# ce3_redraw.net
KiCad netlist of a schematic drawn in EAGLE
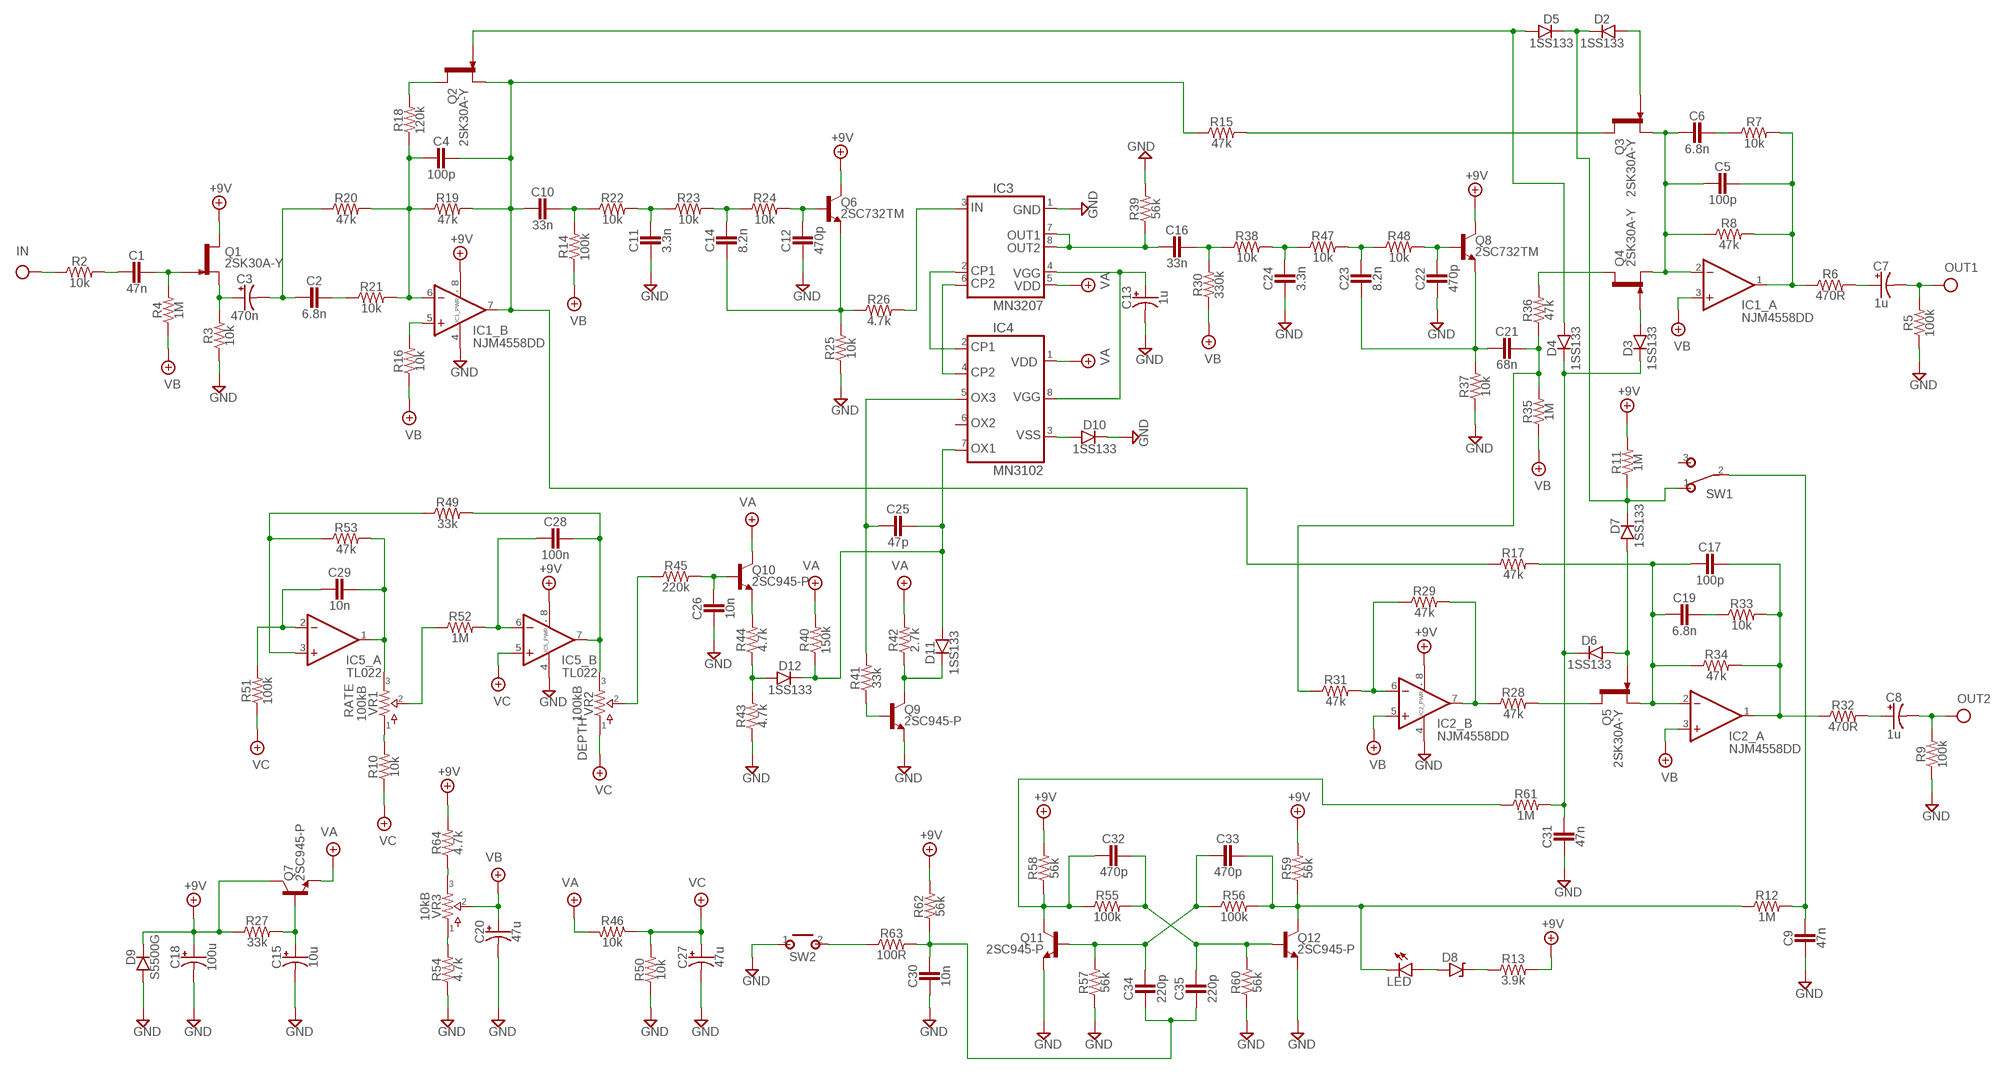
[diagram p0: schematic, sheet 1]

(export (version "E")
  (design (tool "Eeschema 10.0.6"))
  (components
    (comp (ref "C1")
      (value "47n")
      (footprint "eagle-import:BOX_SMALL")
      (libsource (lib "eagle-import") (part "CER/FILMBOX.1"))
    )
    (comp (ref "C2")
      (value "6.8n")
      (footprint "eagle-import:BOX_SMALL")
      (libsource (lib "eagle-import") (part "CER/FILMBOX.1"))
    )
    (comp (ref "C3")
      (value "470n")
      (footprint "eagle-import:040_020")
      (libsource (lib "eagle-import") (part "0400"))
    )
    (comp (ref "C4")
      (value "100p")
      (footprint "eagle-import:BOX_SMALL")
      (libsource (lib "eagle-import") (part "CER/FILMBOX.1"))
    )
    (comp (ref "C5")
      (value "100p")
      (footprint "eagle-import:BOX_SMALL")
      (libsource (lib "eagle-import") (part "CER/FILMBOX.1"))
    )
    (comp (ref "C6")
      (value "6.8n")
      (footprint "eagle-import:BOX_SMALL")
      (libsource (lib "eagle-import") (part "CER/FILMBOX.1"))
    )
    (comp (ref "C7")
      (value "1u")
      (footprint "eagle-import:040_020")
      (libsource (lib "eagle-import") (part "0400"))
    )
    (comp (ref "C8")
      (value "1u")
      (footprint "eagle-import:040_020")
      (libsource (lib "eagle-import") (part "0400"))
    )
    (comp (ref "C9")
      (value "47n")
      (footprint "eagle-import:BOX_SMALL")
      (libsource (lib "eagle-import") (part "CER/FILMBOX.1"))
    )
    (comp (ref "C10")
      (value "33n")
      (footprint "eagle-import:BOX_SMALL")
      (libsource (lib "eagle-import") (part "CER/FILMBOX.1"))
    )
    (comp (ref "C11")
      (value "3.3n")
      (footprint "eagle-import:BOX_SMALL")
      (libsource (lib "eagle-import") (part "CER/FILMBOX.1"))
    )
    (comp (ref "C12")
      (value "470p")
      (footprint "eagle-import:BOX_SMALL")
      (libsource (lib "eagle-import") (part "CER/FILMBOX.1"))
    )
    (comp (ref "C13")
      (value "1u")
      (footprint "eagle-import:040_020")
      (libsource (lib "eagle-import") (part "0400"))
    )
    (comp (ref "C14")
      (value "8.2n")
      (footprint "eagle-import:BOX_SMALL")
      (libsource (lib "eagle-import") (part "CER/FILMBOX.1"))
    )
    (comp (ref "C15")
      (value "10u")
      (footprint "eagle-import:040_020")
      (libsource (lib "eagle-import") (part "0400"))
    )
    (comp (ref "C16")
      (value "33n")
      (footprint "eagle-import:BOX_SMALL")
      (libsource (lib "eagle-import") (part "CER/FILMBOX.1"))
    )
    (comp (ref "C17")
      (value "100p")
      (footprint "eagle-import:BOX_SMALL")
      (libsource (lib "eagle-import") (part "CER/FILMBOX.1"))
    )
    (comp (ref "C18")
      (value "100u")
      (footprint "eagle-import:040_020")
      (libsource (lib "eagle-import") (part "0400"))
    )
    (comp (ref "C19")
      (value "6.8n")
      (footprint "eagle-import:BOX_SMALL")
      (libsource (lib "eagle-import") (part "CER/FILMBOX.1"))
    )
    (comp (ref "C20")
      (value "47u")
      (footprint "eagle-import:040_020")
      (libsource (lib "eagle-import") (part "0400"))
    )
    (comp (ref "C21")
      (value "68n")
      (footprint "eagle-import:BOX_SMALL")
      (libsource (lib "eagle-import") (part "CER/FILMBOX.1"))
    )
    (comp (ref "C22")
      (value "470p")
      (footprint "eagle-import:BOX_SMALL")
      (libsource (lib "eagle-import") (part "CER/FILMBOX.1"))
    )
    (comp (ref "C23")
      (value "8.2n")
      (footprint "eagle-import:BOX_SMALL")
      (libsource (lib "eagle-import") (part "CER/FILMBOX.1"))
    )
    (comp (ref "C24")
      (value "3.3n")
      (footprint "eagle-import:BOX_SMALL")
      (libsource (lib "eagle-import") (part "CER/FILMBOX.1"))
    )
    (comp (ref "C25")
      (value "47p")
      (footprint "eagle-import:BOX_SMALL")
      (libsource (lib "eagle-import") (part "CER/FILMBOX.1"))
    )
    (comp (ref "C26")
      (value "10n")
      (footprint "eagle-import:BOX_SMALL")
      (libsource (lib "eagle-import") (part "CER/FILMBOX.1"))
    )
    (comp (ref "C27")
      (value "47u")
      (footprint "eagle-import:040_020")
      (libsource (lib "eagle-import") (part "0400"))
    )
    (comp (ref "C28")
      (value "100n")
      (footprint "eagle-import:BOX_SMALL")
      (libsource (lib "eagle-import") (part "CER/FILMBOX.1"))
    )
    (comp (ref "C29")
      (value "10n")
      (footprint "eagle-import:BOX_SMALL")
      (libsource (lib "eagle-import") (part "CER/FILMBOX.1"))
    )
    (comp (ref "C30")
      (value "10n")
      (footprint "eagle-import:BOX_SMALL")
      (libsource (lib "eagle-import") (part "CER/FILMBOX.1"))
    )
    (comp (ref "C31")
      (value "47n")
      (footprint "eagle-import:BOX_SMALL")
      (libsource (lib "eagle-import") (part "CER/FILMBOX.1"))
    )
    (comp (ref "C32")
      (value "470p")
      (footprint "eagle-import:BOX_SMALL")
      (libsource (lib "eagle-import") (part "CER/FILMBOX.1"))
    )
    (comp (ref "C33")
      (value "470p")
      (footprint "eagle-import:BOX_SMALL")
      (libsource (lib "eagle-import") (part "CER/FILMBOX.1"))
    )
    (comp (ref "C34")
      (value "220p")
      (footprint "eagle-import:BOX_SMALL")
      (libsource (lib "eagle-import") (part "CER/FILMBOX.1"))
    )
    (comp (ref "C35")
      (value "220p")
      (footprint "eagle-import:BOX_SMALL")
      (libsource (lib "eagle-import") (part "CER/FILMBOX.1"))
    )
    (comp (ref "D2")
      (value "1SS133")
      (footprint "eagle-import:DO35-2")
      (libsource (lib "eagle-import") (part "DO35.2"))
    )
    (comp (ref "D3")
      (value "1SS133")
      (footprint "eagle-import:DO35-2")
      (libsource (lib "eagle-import") (part "DO35.2"))
    )
    (comp (ref "D4")
      (value "1SS133")
      (footprint "eagle-import:DO35-2")
      (libsource (lib "eagle-import") (part "DO35.2"))
    )
    (comp (ref "D5")
      (value "1SS133")
      (footprint "eagle-import:DO35-2")
      (libsource (lib "eagle-import") (part "DO35.2"))
    )
    (comp (ref "D6")
      (value "1SS133")
      (footprint "eagle-import:DO35-2")
      (libsource (lib "eagle-import") (part "DO35.2"))
    )
    (comp (ref "D7")
      (value "1SS133")
      (footprint "eagle-import:DO35-2")
      (libsource (lib "eagle-import") (part "DO35.2"))
    )
    (comp (ref "D8")
      (value "ZENER.2")
      (footprint "eagle-import:DO41-2")
      (libsource (lib "eagle-import") (part "ZENER.2"))
    )
    (comp (ref "D9")
      (value "S5500G")
      (footprint "eagle-import:DO35-2")
      (libsource (lib "eagle-import") (part "DO35.2"))
    )
    (comp (ref "D10")
      (value "1SS133")
      (footprint "eagle-import:DO35-2")
      (libsource (lib "eagle-import") (part "DO35.2"))
    )
    (comp (ref "D11")
      (value "1SS133")
      (footprint "eagle-import:DO35-2")
      (libsource (lib "eagle-import") (part "DO35.2"))
    )
    (comp (ref "D12")
      (value "1SS133")
      (footprint "eagle-import:DO35-2")
      (libsource (lib "eagle-import") (part "DO35.2"))
    )
    (comp (ref "IC1")
      (value "NJM4558DD")
      (footprint "eagle-import:DIL0")
      (libsource (lib "eagle-import") (part "DUALTH"))
    )
    (comp (ref "IC2")
      (value "NJM4558DD")
      (footprint "eagle-import:DIL0")
      (libsource (lib "eagle-import") (part "DUALTH"))
    )
    (comp (ref "IC3")
      (value "MN3207")
      (footprint "eagle-import:DIL0")
      (libsource (lib "eagle-import") (part "BL3208"))
    )
    (comp (ref "IC4")
      (value "MN3102")
      (footprint "eagle-import:DIL8")
      (libsource (lib "eagle-import") (part "CLOCK"))
    )
    (comp (ref "IC5")
      (value "TL022")
      (footprint "eagle-import:DIL0")
      (libsource (lib "eagle-import") (part "DUALTH"))
    )
    (comp (ref "LED")
      (value "LED")
      (footprint "eagle-import:3MM_D")
      (libsource (lib "eagle-import") (part "LED"))
    )
    (comp (ref "Q1")
      (value "2SK30A-Y")
      (footprint "eagle-import:TO92-")
      (libsource (lib "eagle-import") (part "2N5457"))
    )
    (comp (ref "Q2")
      (value "2SK30A-Y")
      (footprint "eagle-import:TO92-")
      (libsource (lib "eagle-import") (part "2N5457"))
    )
    (comp (ref "Q3")
      (value "2SK30A-Y")
      (footprint "eagle-import:TO92-")
      (libsource (lib "eagle-import") (part "2N5457"))
    )
    (comp (ref "Q4")
      (value "2SK30A-Y")
      (footprint "eagle-import:TO92-")
      (libsource (lib "eagle-import") (part "2N5457"))
    )
    (comp (ref "Q5")
      (value "2SK30A-Y")
      (footprint "eagle-import:TO92-")
      (libsource (lib "eagle-import") (part "2N5457"))
    )
    (comp (ref "Q6")
      (value "2SC732TM")
      (footprint "eagle-import:TO92-")
      (libsource (lib "eagle-import") (part "2SC828A"))
    )
    (comp (ref "Q7")
      (value "2SC945-P")
      (footprint "eagle-import:TO92-")
      (libsource (lib "eagle-import") (part "2SC828A"))
    )
    (comp (ref "Q8")
      (value "2SC732TM")
      (footprint "eagle-import:TO92-")
      (libsource (lib "eagle-import") (part "2SC828A"))
    )
    (comp (ref "Q9")
      (value "2SC945-P")
      (footprint "eagle-import:TO92-")
      (libsource (lib "eagle-import") (part "2SC828A"))
    )
    (comp (ref "Q10")
      (value "2SC945-P")
      (footprint "eagle-import:TO92-")
      (libsource (lib "eagle-import") (part "2SC828A"))
    )
    (comp (ref "Q11")
      (value "2SC945-P")
      (footprint "eagle-import:TO92-")
      (libsource (lib "eagle-import") (part "2SC828A"))
    )
    (comp (ref "Q12")
      (value "2SC945-P")
      (footprint "eagle-import:TO92-")
      (libsource (lib "eagle-import") (part "2SC828A"))
    )
    (comp (ref "R2")
      (value "10k")
      (footprint "eagle-import:R0207_3")
      (libsource (lib "eagle-import") (part "R_.3B"))
    )
    (comp (ref "R3")
      (value "10k")
      (footprint "eagle-import:R0207_3")
      (libsource (lib "eagle-import") (part "R_.3B"))
    )
    (comp (ref "R4")
      (value "1M")
      (footprint "eagle-import:R0207_3")
      (libsource (lib "eagle-import") (part "R_.3B"))
    )
    (comp (ref "R5")
      (value "100k")
      (footprint "eagle-import:R0207_3")
      (libsource (lib "eagle-import") (part "R_.3B"))
    )
    (comp (ref "R6")
      (value "470R")
      (footprint "eagle-import:R0207_3")
      (libsource (lib "eagle-import") (part "R_.3B"))
    )
    (comp (ref "R7")
      (value "10k")
      (footprint "eagle-import:R0207_3")
      (libsource (lib "eagle-import") (part "R_.3B"))
    )
    (comp (ref "R8")
      (value "47k")
      (footprint "eagle-import:R0207_3")
      (libsource (lib "eagle-import") (part "R_.3B"))
    )
    (comp (ref "R9")
      (value "100k")
      (footprint "eagle-import:R0207_3")
      (libsource (lib "eagle-import") (part "R_.3B"))
    )
    (comp (ref "R10")
      (value "10k")
      (footprint "eagle-import:R0207_3")
      (libsource (lib "eagle-import") (part "R_.3B"))
    )
    (comp (ref "R11")
      (value "1M")
      (footprint "eagle-import:R0207_3")
      (libsource (lib "eagle-import") (part "R_.3B"))
    )
    (comp (ref "R12")
      (value "1M")
      (footprint "eagle-import:R0207_3")
      (libsource (lib "eagle-import") (part "R_.3B"))
    )
    (comp (ref "R13")
      (value "3.9k")
      (footprint "eagle-import:R0207_3")
      (libsource (lib "eagle-import") (part "R_.3B"))
    )
    (comp (ref "R14")
      (value "100k")
      (footprint "eagle-import:R0207_3")
      (libsource (lib "eagle-import") (part "R_.3B"))
    )
    (comp (ref "R15")
      (value "47k")
      (footprint "eagle-import:R0207_3")
      (libsource (lib "eagle-import") (part "R_.3B"))
    )
    (comp (ref "R16")
      (value "10k")
      (footprint "eagle-import:R0207_3")
      (libsource (lib "eagle-import") (part "R_.3B"))
    )
    (comp (ref "R17")
      (value "47k")
      (footprint "eagle-import:R0207_3")
      (libsource (lib "eagle-import") (part "R_.3B"))
    )
    (comp (ref "R18")
      (value "120k")
      (footprint "eagle-import:R0207_3")
      (libsource (lib "eagle-import") (part "R_.3B"))
    )
    (comp (ref "R19")
      (value "47k")
      (footprint "eagle-import:R0207_3")
      (libsource (lib "eagle-import") (part "R_.3B"))
    )
    (comp (ref "R20")
      (value "47k")
      (footprint "eagle-import:R0207_3")
      (libsource (lib "eagle-import") (part "R_.3B"))
    )
    (comp (ref "R21")
      (value "10k")
      (footprint "eagle-import:R0207_3")
      (libsource (lib "eagle-import") (part "R_.3B"))
    )
    (comp (ref "R22")
      (value "10k")
      (footprint "eagle-import:R0207_3")
      (libsource (lib "eagle-import") (part "R_.3B"))
    )
    (comp (ref "R23")
      (value "10k")
      (footprint "eagle-import:R0207_3")
      (libsource (lib "eagle-import") (part "R_.3B"))
    )
    (comp (ref "R24")
      (value "10k")
      (footprint "eagle-import:R0207_3")
      (libsource (lib "eagle-import") (part "R_.3B"))
    )
    (comp (ref "R25")
      (value "10k")
      (footprint "eagle-import:R0207_3")
      (libsource (lib "eagle-import") (part "R_.3B"))
    )
    (comp (ref "R26")
      (value "4.7k")
      (footprint "eagle-import:R0207_3")
      (libsource (lib "eagle-import") (part "R_.3B"))
    )
    (comp (ref "R27")
      (value "33k")
      (footprint "eagle-import:R0207_3")
      (libsource (lib "eagle-import") (part "R_.3B"))
    )
    (comp (ref "R28")
      (value "47k")
      (footprint "eagle-import:R0207_3")
      (libsource (lib "eagle-import") (part "R_.3B"))
    )
    (comp (ref "R29")
      (value "47k")
      (footprint "eagle-import:R0207_3")
      (libsource (lib "eagle-import") (part "R_.3B"))
    )
    (comp (ref "R30")
      (value "330k")
      (footprint "eagle-import:R0207_3")
      (libsource (lib "eagle-import") (part "R_.3B"))
    )
    (comp (ref "R31")
      (value "47k")
      (footprint "eagle-import:R0207_3")
      (libsource (lib "eagle-import") (part "R_.3B"))
    )
    (comp (ref "R32")
      (value "470R")
      (footprint "eagle-import:R0207_3")
      (libsource (lib "eagle-import") (part "R_.3B"))
    )
    (comp (ref "R33")
      (value "10k")
      (footprint "eagle-import:R0207_3")
      (libsource (lib "eagle-import") (part "R_.3B"))
    )
    (comp (ref "R34")
      (value "47k")
      (footprint "eagle-import:R0207_3")
      (libsource (lib "eagle-import") (part "R_.3B"))
    )
    (comp (ref "R35")
      (value "1M")
      (footprint "eagle-import:R0207_3")
      (libsource (lib "eagle-import") (part "R_.3B"))
    )
    (comp (ref "R36")
      (value "47k")
      (footprint "eagle-import:R0207_3")
      (libsource (lib "eagle-import") (part "R_.3B"))
    )
    (comp (ref "R37")
      (value "10k")
      (footprint "eagle-import:R0207_3")
      (libsource (lib "eagle-import") (part "R_.3B"))
    )
    (comp (ref "R38")
      (value "10k")
      (footprint "eagle-import:R0207_3")
      (libsource (lib "eagle-import") (part "R_.3B"))
    )
    (comp (ref "R39")
      (value "56k")
      (footprint "eagle-import:R0207_3")
      (libsource (lib "eagle-import") (part "R_.3B"))
    )
    (comp (ref "R40")
      (value "150k")
      (footprint "eagle-import:R0207_3")
      (libsource (lib "eagle-import") (part "R_.3B"))
    )
    (comp (ref "R41")
      (value "33k")
      (footprint "eagle-import:R0207_3")
      (libsource (lib "eagle-import") (part "R_.3B"))
    )
    (comp (ref "R42")
      (value "2.7k")
      (footprint "eagle-import:R0207_3")
      (libsource (lib "eagle-import") (part "R_.3B"))
    )
    (comp (ref "R43")
      (value "4.7k")
      (footprint "eagle-import:R0207_3")
      (libsource (lib "eagle-import") (part "R_.3B"))
    )
    (comp (ref "R44")
      (value "4.7k")
      (footprint "eagle-import:R0207_3")
      (libsource (lib "eagle-import") (part "R_.3B"))
    )
    (comp (ref "R45")
      (value "220k")
      (footprint "eagle-import:R0207_3")
      (libsource (lib "eagle-import") (part "R_.3B"))
    )
    (comp (ref "R46")
      (value "10k")
      (footprint "eagle-import:R0207_3")
      (libsource (lib "eagle-import") (part "R_.3B"))
    )
    (comp (ref "R47")
      (value "10k")
      (footprint "eagle-import:R0207_3")
      (libsource (lib "eagle-import") (part "R_.3B"))
    )
    (comp (ref "R48")
      (value "10k")
      (footprint "eagle-import:R0207_3")
      (libsource (lib "eagle-import") (part "R_.3B"))
    )
    (comp (ref "R49")
      (value "33k")
      (footprint "eagle-import:R0207_3")
      (libsource (lib "eagle-import") (part "R_.3B"))
    )
    (comp (ref "R50")
      (value "10k")
      (footprint "eagle-import:R0207_3")
      (libsource (lib "eagle-import") (part "R_.3B"))
    )
    (comp (ref "R51")
      (value "100k")
      (footprint "eagle-import:R0207_3")
      (libsource (lib "eagle-import") (part "R_.3B"))
    )
    (comp (ref "R52")
      (value "1M")
      (footprint "eagle-import:R0207_3")
      (libsource (lib "eagle-import") (part "R_.3B"))
    )
    (comp (ref "R53")
      (value "47k")
      (footprint "eagle-import:R0207_3")
      (libsource (lib "eagle-import") (part "R_.3B"))
    )
    (comp (ref "R54")
      (value "4.7k")
      (footprint "eagle-import:R0207_3")
      (libsource (lib "eagle-import") (part "R_.3B"))
    )
    (comp (ref "R55")
      (value "100k")
      (footprint "eagle-import:R0207_3")
      (libsource (lib "eagle-import") (part "R_.3B"))
    )
    (comp (ref "R56")
      (value "100k")
      (footprint "eagle-import:R0207_3")
      (libsource (lib "eagle-import") (part "R_.3B"))
    )
    (comp (ref "R57")
      (value "56k")
      (footprint "eagle-import:R0207_3")
      (libsource (lib "eagle-import") (part "R_.3B"))
    )
    (comp (ref "R58")
      (value "56k")
      (footprint "eagle-import:R0207_3")
      (libsource (lib "eagle-import") (part "R_.3B"))
    )
    (comp (ref "R59")
      (value "56k")
      (footprint "eagle-import:R0207_3")
      (libsource (lib "eagle-import") (part "R_.3B"))
    )
    (comp (ref "R60")
      (value "56k")
      (footprint "eagle-import:R0207_3")
      (libsource (lib "eagle-import") (part "R_.3B"))
    )
    (comp (ref "R61")
      (value "1M")
      (footprint "eagle-import:R0207_3")
      (libsource (lib "eagle-import") (part "R_.3B"))
    )
    (comp (ref "R62")
      (value "56k")
      (footprint "eagle-import:R0207_3")
      (libsource (lib "eagle-import") (part "R_.3B"))
    )
    (comp (ref "R63")
      (value "100R")
      (footprint "eagle-import:R0207_3")
      (libsource (lib "eagle-import") (part "R_.3B"))
    )
    (comp (ref "R64")
      (value "4.7k")
      (footprint "eagle-import:R0207_3")
      (libsource (lib "eagle-import") (part "R_.3B"))
    )
    (comp (ref "SW1")
      (value "SPDT")
      (footprint "eagle-import:M9040P")
      (libsource (lib "eagle-import") (part "SPDT"))
    )
    (comp (ref "SW2")
      (value "MOMENTARY")
      (footprint "eagle-import:SPST")
      (libsource (lib "eagle-import") (part "MOMENTARY"))
    )
    (comp (ref "VR1")
      (value "100kB")
      (footprint "eagle-import:16MM")
      (libsource (lib "eagle-import") (part "POTS16MM"))
    )
    (comp (ref "VR2")
      (value "100kB")
      (footprint "eagle-import:16MM")
      (libsource (lib "eagle-import") (part "POTS16MM"))
    )
    (comp (ref "VR3")
      (value "10kB")
      (footprint "eagle-import:16MM")
      (libsource (lib "eagle-import") (part "POTS16MM"))
    )
  )
  (nets
    (net (code "1") (name "+9V") (class "Default")
      (node (ref "C18") (pin "+") (pinfunction "+_+") (pintype "passive"))
      (node (ref "D9") (pin "C") (pinfunction "C_C") (pintype "passive"))
      (node (ref "IC1") (pin "8") (pinfunction "V+_8") (pintype "power_in"))
      (node (ref "IC2") (pin "8") (pinfunction "V+_8") (pintype "power_in"))
      (node (ref "IC5") (pin "8") (pinfunction "V+_8") (pintype "power_in"))
      (node (ref "Q1") (pin "3") (pinfunction "D_3") (pintype "passive"))
      (node (ref "Q6") (pin "2") (pinfunction "C_2") (pintype "passive"))
      (node (ref "Q7") (pin "2") (pinfunction "C_2") (pintype "passive"))
      (node (ref "Q8") (pin "2") (pinfunction "C_2") (pintype "passive"))
      (node (ref "R11") (pin "2") (pinfunction "2_2") (pintype "passive"))
      (node (ref "R13") (pin "2") (pinfunction "2_2") (pintype "passive"))
      (node (ref "R27") (pin "1") (pinfunction "1_1") (pintype "passive"))
      (node (ref "R58") (pin "2") (pinfunction "2_2") (pintype "passive"))
      (node (ref "R59") (pin "2") (pinfunction "2_2") (pintype "passive"))
      (node (ref "R62") (pin "2") (pinfunction "2_2") (pintype "passive"))
      (node (ref "R64") (pin "2") (pinfunction "2_2") (pintype "passive"))
    )
    (net (code "2") (name "GND") (class "Default")
      (node (ref "C11") (pin "2") (pinfunction "2_2") (pintype "passive"))
      (node (ref "C12") (pin "2") (pinfunction "2_2") (pintype "passive"))
      (node (ref "C13") (pin "-") (pinfunction "-_-") (pintype "passive"))
      (node (ref "C15") (pin "-") (pinfunction "-_-") (pintype "passive"))
      (node (ref "C18") (pin "-") (pinfunction "-_-") (pintype "passive"))
      (node (ref "C20") (pin "-") (pinfunction "-_-") (pintype "passive"))
      (node (ref "C22") (pin "2") (pinfunction "2_2") (pintype "passive"))
      (node (ref "C24") (pin "2") (pinfunction "2_2") (pintype "passive"))
      (node (ref "C26") (pin "2") (pinfunction "2_2") (pintype "passive"))
      (node (ref "C27") (pin "-") (pinfunction "-_-") (pintype "passive"))
      (node (ref "C30") (pin "2") (pinfunction "2_2") (pintype "passive"))
      (node (ref "C31") (pin "2") (pinfunction "2_2") (pintype "passive"))
      (node (ref "C9") (pin "2") (pinfunction "2_2") (pintype "passive"))
      (node (ref "D10") (pin "C") (pinfunction "C_C") (pintype "passive"))
      (node (ref "D9") (pin "A") (pinfunction "A_A") (pintype "passive"))
      (node (ref "IC1") (pin "4") (pinfunction "V-_4") (pintype "power_in"))
      (node (ref "IC2") (pin "4") (pinfunction "V-_4") (pintype "power_in"))
      (node (ref "IC3") (pin "1") (pinfunction "1_1") (pintype "bidirectional"))
      (node (ref "IC5") (pin "4") (pinfunction "V-_4") (pintype "power_in"))
      (node (ref "Q11") (pin "3") (pinfunction "E_3") (pintype "passive"))
      (node (ref "Q12") (pin "3") (pinfunction "E_3") (pintype "passive"))
      (node (ref "Q9") (pin "3") (pinfunction "E_3") (pintype "passive"))
      (node (ref "R25") (pin "1") (pinfunction "1_1") (pintype "passive"))
      (node (ref "R3") (pin "1") (pinfunction "1_1") (pintype "passive"))
      (node (ref "R37") (pin "1") (pinfunction "1_1") (pintype "passive"))
      (node (ref "R39") (pin "2") (pinfunction "2_2") (pintype "passive"))
      (node (ref "R43") (pin "1") (pinfunction "1_1") (pintype "passive"))
      (node (ref "R5") (pin "1") (pinfunction "1_1") (pintype "passive"))
      (node (ref "R50") (pin "1") (pinfunction "1_1") (pintype "passive"))
      (node (ref "R54") (pin "1") (pinfunction "1_1") (pintype "passive"))
      (node (ref "R57") (pin "1") (pinfunction "1_1") (pintype "passive"))
      (node (ref "R60") (pin "1") (pinfunction "1_1") (pintype "passive"))
      (node (ref "R9") (pin "1") (pinfunction "1_1") (pintype "passive"))
      (node (ref "SW2") (pin "1") (pinfunction "P_1") (pintype "passive"))
    )
    (net (code "3") (name "IN") (class "Default")
      (node (ref "R2") (pin "1") (pinfunction "1_1") (pintype "passive"))
    )
    (net (code "4") (name "Net-(C1-Pad2)") (class "Default")
      (node (ref "C1") (pin "2") (pinfunction "2_2") (pintype "passive"))
      (node (ref "R2") (pin "2") (pinfunction "2_2") (pintype "passive"))
    )
    (net (code "5") (name "Net-(C2-Pad1)") (class "Default")
      (node (ref "C2") (pin "1") (pinfunction "1_1") (pintype "passive"))
      (node (ref "R21") (pin "1") (pinfunction "1_1") (pintype "passive"))
    )
    (net (code "6") (name "Net-(C2-Pad2)") (class "Default")
      (node (ref "C2") (pin "2") (pinfunction "2_2") (pintype "passive"))
      (node (ref "C3") (pin "-") (pinfunction "-_-") (pintype "passive"))
      (node (ref "R20") (pin "1") (pinfunction "1_1") (pintype "passive"))
    )
    (net (code "7") (name "Net-(C6-Pad1)") (class "Default")
      (node (ref "C6") (pin "1") (pinfunction "1_1") (pintype "passive"))
      (node (ref "R7") (pin "1") (pinfunction "1_1") (pintype "passive"))
    )
    (net (code "8") (name "Net-(C7-Pad+)") (class "Default")
      (node (ref "C7") (pin "+") (pinfunction "+_+") (pintype "passive"))
      (node (ref "R6") (pin "2") (pinfunction "2_2") (pintype "passive"))
    )
    (net (code "9") (name "Net-(C8-Pad+)") (class "Default")
      (node (ref "C8") (pin "+") (pinfunction "+_+") (pintype "passive"))
      (node (ref "R32") (pin "2") (pinfunction "2_2") (pintype "passive"))
    )
    (net (code "10") (name "Net-(C10-Pad1)") (class "Default")
      (node (ref "C10") (pin "1") (pinfunction "1_1") (pintype "passive"))
      (node (ref "R14") (pin "2") (pinfunction "2_2") (pintype "passive"))
      (node (ref "R22") (pin "1") (pinfunction "1_1") (pintype "passive"))
    )
    (net (code "11") (name "Net-(C11-Pad1)") (class "Default")
      (node (ref "C11") (pin "1") (pinfunction "1_1") (pintype "passive"))
      (node (ref "R22") (pin "2") (pinfunction "2_2") (pintype "passive"))
      (node (ref "R23") (pin "1") (pinfunction "1_1") (pintype "passive"))
    )
    (net (code "12") (name "Net-(C14-Pad1)") (class "Default")
      (node (ref "C14") (pin "1") (pinfunction "1_1") (pintype "passive"))
      (node (ref "R23") (pin "2") (pinfunction "2_2") (pintype "passive"))
      (node (ref "R24") (pin "1") (pinfunction "1_1") (pintype "passive"))
    )
    (net (code "13") (name "Net-(C16-Pad1)") (class "Default")
      (node (ref "C16") (pin "1") (pinfunction "1_1") (pintype "passive"))
      (node (ref "R30") (pin "2") (pinfunction "2_2") (pintype "passive"))
      (node (ref "R38") (pin "1") (pinfunction "1_1") (pintype "passive"))
    )
    (net (code "14") (name "Net-(C16-Pad2)") (class "Default")
      (node (ref "C16") (pin "2") (pinfunction "2_2") (pintype "passive"))
      (node (ref "IC3") (pin "7") (pinfunction "7_7") (pintype "bidirectional"))
      (node (ref "IC3") (pin "8") (pinfunction "8_8") (pintype "bidirectional"))
      (node (ref "R39") (pin "1") (pinfunction "1_1") (pintype "passive"))
    )
    (net (code "15") (name "Net-(C19-Pad1)") (class "Default")
      (node (ref "C19") (pin "1") (pinfunction "1_1") (pintype "passive"))
      (node (ref "R33") (pin "1") (pinfunction "1_1") (pintype "passive"))
    )
    (net (code "16") (name "Net-(C21-Pad1)") (class "Default")
      (node (ref "C21") (pin "1") (pinfunction "1_1") (pintype "passive"))
      (node (ref "R31") (pin "1") (pinfunction "1_1") (pintype "passive"))
      (node (ref "R35") (pin "2") (pinfunction "2_2") (pintype "passive"))
      (node (ref "R36") (pin "1") (pinfunction "1_1") (pintype "passive"))
    )
    (net (code "17") (name "Net-(C23-Pad1)") (class "Default")
      (node (ref "C23") (pin "1") (pinfunction "1_1") (pintype "passive"))
      (node (ref "R47") (pin "2") (pinfunction "2_2") (pintype "passive"))
      (node (ref "R48") (pin "1") (pinfunction "1_1") (pintype "passive"))
    )
    (net (code "18") (name "Net-(C24-Pad1)") (class "Default")
      (node (ref "C24") (pin "1") (pinfunction "1_1") (pintype "passive"))
      (node (ref "R38") (pin "2") (pinfunction "2_2") (pintype "passive"))
      (node (ref "R47") (pin "1") (pinfunction "1_1") (pintype "passive"))
    )
    (net (code "19") (name "Net-(C30-Pad1)") (class "Default")
      (node (ref "C30") (pin "1") (pinfunction "1_1") (pintype "passive"))
      (node (ref "C34") (pin "2") (pinfunction "2_2") (pintype "passive"))
      (node (ref "C35") (pin "2") (pinfunction "2_2") (pintype "passive"))
      (node (ref "R62") (pin "1") (pinfunction "1_1") (pintype "passive"))
      (node (ref "R63") (pin "2") (pinfunction "2_2") (pintype "passive"))
    )
    (net (code "20") (name "Net-(C31-Pad1)") (class "Default")
      (node (ref "C31") (pin "1") (pinfunction "1_1") (pintype "passive"))
      (node (ref "D3") (pin "C") (pinfunction "C_C") (pintype "passive"))
      (node (ref "D4") (pin "C") (pinfunction "C_C") (pintype "passive"))
      (node (ref "D6") (pin "C") (pinfunction "C_C") (pintype "passive"))
      (node (ref "R61") (pin "2") (pinfunction "2_2") (pintype "passive"))
    )
    (net (code "21") (name "Net-(D8-PadC)") (class "Default")
      (node (ref "D8") (pin "C") (pinfunction "C_C") (pintype "passive"))
      (node (ref "R13") (pin "1") (pinfunction "1_1") (pintype "passive"))
    )
    (net (code "22") (name "Net-(D12-PadA)") (class "Default")
      (node (ref "D12") (pin "A") (pinfunction "A_A") (pintype "passive"))
      (node (ref "R43") (pin "2") (pinfunction "2_2") (pintype "passive"))
      (node (ref "R44") (pin "1") (pinfunction "1_1") (pintype "passive"))
    )
    (net (code "23") (name "Net-(IC1A--IN)") (class "Default")
      (node (ref "C5") (pin "2") (pinfunction "2_2") (pintype "passive"))
      (node (ref "C6") (pin "2") (pinfunction "2_2") (pintype "passive"))
      (node (ref "IC1") (pin "2") (pinfunction "-IN_2") (pintype "input"))
      (node (ref "Q3") (pin "2") (pinfunction "S_2") (pintype "passive"))
      (node (ref "Q4") (pin "2") (pinfunction "S_2") (pintype "passive"))
      (node (ref "R8") (pin "1") (pinfunction "1_1") (pintype "passive"))
    )
    (net (code "24") (name "Net-(IC1A-OUT)") (class "Default")
      (node (ref "C5") (pin "1") (pinfunction "1_1") (pintype "passive"))
      (node (ref "IC1") (pin "1") (pinfunction "OUT_1") (pintype "output"))
      (node (ref "R6") (pin "1") (pinfunction "1_1") (pintype "passive"))
      (node (ref "R7") (pin "2") (pinfunction "2_2") (pintype "passive"))
      (node (ref "R8") (pin "2") (pinfunction "2_2") (pintype "passive"))
    )
    (net (code "25") (name "Net-(IC1B-+IN)") (class "Default")
      (node (ref "IC1") (pin "5") (pinfunction "+IN_5") (pintype "input"))
      (node (ref "R16") (pin "2") (pinfunction "2_2") (pintype "passive"))
    )
    (net (code "26") (name "Net-(IC1B--IN)") (class "Default")
      (node (ref "C4") (pin "2") (pinfunction "2_2") (pintype "passive"))
      (node (ref "IC1") (pin "6") (pinfunction "-IN_6") (pintype "input"))
      (node (ref "R18") (pin "1") (pinfunction "1_1") (pintype "passive"))
      (node (ref "R19") (pin "1") (pinfunction "1_1") (pintype "passive"))
      (node (ref "R20") (pin "2") (pinfunction "2_2") (pintype "passive"))
      (node (ref "R21") (pin "2") (pinfunction "2_2") (pintype "passive"))
    )
    (net (code "27") (name "Net-(IC1B-OUT)") (class "Default")
      (node (ref "C10") (pin "2") (pinfunction "2_2") (pintype "passive"))
      (node (ref "C4") (pin "1") (pinfunction "1_1") (pintype "passive"))
      (node (ref "IC1") (pin "7") (pinfunction "OUT_7") (pintype "output"))
      (node (ref "Q2") (pin "2") (pinfunction "S_2") (pintype "passive"))
      (node (ref "R15") (pin "1") (pinfunction "1_1") (pintype "passive"))
      (node (ref "R17") (pin "1") (pinfunction "1_1") (pintype "passive"))
      (node (ref "R19") (pin "2") (pinfunction "2_2") (pintype "passive"))
    )
    (net (code "28") (name "Net-(IC2A--IN)") (class "Default")
      (node (ref "C17") (pin "2") (pinfunction "2_2") (pintype "passive"))
      (node (ref "C19") (pin "2") (pinfunction "2_2") (pintype "passive"))
      (node (ref "IC2") (pin "2") (pinfunction "-IN_2") (pintype "input"))
      (node (ref "Q5") (pin "2") (pinfunction "S_2") (pintype "passive"))
      (node (ref "R17") (pin "2") (pinfunction "2_2") (pintype "passive"))
      (node (ref "R34") (pin "1") (pinfunction "1_1") (pintype "passive"))
    )
    (net (code "29") (name "Net-(IC2A-OUT)") (class "Default")
      (node (ref "C17") (pin "1") (pinfunction "1_1") (pintype "passive"))
      (node (ref "IC2") (pin "1") (pinfunction "OUT_1") (pintype "output"))
      (node (ref "R32") (pin "1") (pinfunction "1_1") (pintype "passive"))
      (node (ref "R33") (pin "2") (pinfunction "2_2") (pintype "passive"))
      (node (ref "R34") (pin "2") (pinfunction "2_2") (pintype "passive"))
    )
    (net (code "30") (name "Net-(IC2B--IN)") (class "Default")
      (node (ref "IC2") (pin "6") (pinfunction "-IN_6") (pintype "input"))
      (node (ref "R29") (pin "1") (pinfunction "1_1") (pintype "passive"))
      (node (ref "R31") (pin "2") (pinfunction "2_2") (pintype "passive"))
    )
    (net (code "31") (name "Net-(IC2B-OUT)") (class "Default")
      (node (ref "IC2") (pin "7") (pinfunction "OUT_7") (pintype "output"))
      (node (ref "R28") (pin "1") (pinfunction "1_1") (pintype "passive"))
      (node (ref "R29") (pin "2") (pinfunction "2_2") (pintype "passive"))
    )
    (net (code "32") (name "Net-(IC3-Pad3)") (class "Default")
      (node (ref "IC3") (pin "3") (pinfunction "3_3") (pintype "bidirectional"))
      (node (ref "R26") (pin "2") (pinfunction "2_2") (pintype "passive"))
    )
    (net (code "33") (name "Net-(IC4-P$2)") (class "Default")
      (node (ref "IC3") (pin "2") (pinfunction "2_2") (pintype "bidirectional"))
      (node (ref "IC4") (pin "2") (pinfunction "P$2_2") (pintype "bidirectional"))
    )
    (net (code "34") (name "Net-(IC4-P$3)") (class "Default")
      (node (ref "D10") (pin "A") (pinfunction "A_A") (pintype "passive"))
      (node (ref "IC4") (pin "3") (pinfunction "P$3_3") (pintype "bidirectional"))
    )
    (net (code "35") (name "Net-(IC4-P$4)") (class "Default")
      (node (ref "IC3") (pin "6") (pinfunction "6_6") (pintype "bidirectional"))
      (node (ref "IC4") (pin "4") (pinfunction "P$4_4") (pintype "bidirectional"))
    )
    (net (code "36") (name "Net-(IC4-P$5)") (class "Default")
      (node (ref "C25") (pin "2") (pinfunction "2_2") (pintype "passive"))
      (node (ref "IC4") (pin "5") (pinfunction "P$5_5") (pintype "bidirectional"))
      (node (ref "R41") (pin "2") (pinfunction "2_2") (pintype "passive"))
    )
    (net (code "37") (name "Net-(IC4-P$7)") (class "Default")
      (node (ref "C25") (pin "1") (pinfunction "1_1") (pintype "passive"))
      (node (ref "D11") (pin "A") (pinfunction "A_A") (pintype "passive"))
      (node (ref "D12") (pin "C") (pinfunction "C_C") (pintype "passive"))
      (node (ref "IC4") (pin "7") (pinfunction "P$7_7") (pintype "bidirectional"))
      (node (ref "R40") (pin "1") (pinfunction "1_1") (pintype "passive"))
    )
    (net (code "38") (name "Net-(IC4-P$8)") (class "Default")
      (node (ref "C13") (pin "+") (pinfunction "+_+") (pintype "passive"))
      (node (ref "IC3") (pin "4") (pinfunction "4_4") (pintype "bidirectional"))
      (node (ref "IC4") (pin "8") (pinfunction "P$8_8") (pintype "bidirectional"))
    )
    (net (code "39") (name "Net-(IC5A-+IN)") (class "Default")
      (node (ref "IC5") (pin "3") (pinfunction "+IN_3") (pintype "input"))
      (node (ref "R49") (pin "1") (pinfunction "1_1") (pintype "passive"))
      (node (ref "R53") (pin "1") (pinfunction "1_1") (pintype "passive"))
    )
    (net (code "40") (name "Net-(IC5A--IN)") (class "Default")
      (node (ref "C29") (pin "2") (pinfunction "2_2") (pintype "passive"))
      (node (ref "IC5") (pin "2") (pinfunction "-IN_2") (pintype "input"))
      (node (ref "R51") (pin "2") (pinfunction "2_2") (pintype "passive"))
    )
    (net (code "41") (name "Net-(IC5A-OUT)") (class "Default")
      (node (ref "C29") (pin "1") (pinfunction "1_1") (pintype "passive"))
      (node (ref "IC5") (pin "1") (pinfunction "OUT_1") (pintype "output"))
      (node (ref "R53") (pin "2") (pinfunction "2_2") (pintype "passive"))
      (node (ref "VR1") (pin "3") (pinfunction "3_3") (pintype "passive"))
    )
    (net (code "42") (name "Net-(IC5B--IN)") (class "Default")
      (node (ref "C28") (pin "2") (pinfunction "2_2") (pintype "passive"))
      (node (ref "IC5") (pin "6") (pinfunction "-IN_6") (pintype "input"))
      (node (ref "R52") (pin "2") (pinfunction "2_2") (pintype "passive"))
    )
    (net (code "43") (name "Net-(IC5B-OUT)") (class "Default")
      (node (ref "C28") (pin "1") (pinfunction "1_1") (pintype "passive"))
      (node (ref "IC5") (pin "7") (pinfunction "OUT_7") (pintype "output"))
      (node (ref "R49") (pin "2") (pinfunction "2_2") (pintype "passive"))
      (node (ref "VR2") (pin "3") (pinfunction "3_3") (pintype "passive"))
    )
    (net (code "44") (name "Net-(LED-A)") (class "Default")
      (node (ref "D8") (pin "A") (pinfunction "A_A") (pintype "passive"))
      (node (ref "LED") (pin "ANODE") (pinfunction "A_ANODE") (pintype "passive"))
    )
    (net (code "45") (name "Net-(LED-C)") (class "Default")
      (node (ref "C33") (pin "1") (pinfunction "1_1") (pintype "passive"))
      (node (ref "LED") (pin "P$1") (pinfunction "C_P$1") (pintype "passive"))
      (node (ref "Q12") (pin "2") (pinfunction "C_2") (pintype "passive"))
      (node (ref "R12") (pin "1") (pinfunction "1_1") (pintype "passive"))
      (node (ref "R56") (pin "2") (pinfunction "2_2") (pintype "passive"))
      (node (ref "R59") (pin "1") (pinfunction "1_1") (pintype "passive"))
    )
    (net (code "46") (name "Net-(Q1-G)") (class "Default")
      (node (ref "C1") (pin "1") (pinfunction "1_1") (pintype "passive"))
      (node (ref "Q1") (pin "1") (pinfunction "G_1") (pintype "passive"))
      (node (ref "R4") (pin "2") (pinfunction "2_2") (pintype "passive"))
    )
    (net (code "47") (name "Net-(Q1-S)") (class "Default")
      (node (ref "C3") (pin "+") (pinfunction "+_+") (pintype "passive"))
      (node (ref "Q1") (pin "2") (pinfunction "S_2") (pintype "passive"))
      (node (ref "R3") (pin "2") (pinfunction "2_2") (pintype "passive"))
    )
    (net (code "48") (name "Net-(Q2-D)") (class "Default")
      (node (ref "Q2") (pin "3") (pinfunction "D_3") (pintype "passive"))
      (node (ref "R18") (pin "2") (pinfunction "2_2") (pintype "passive"))
    )
    (net (code "49") (name "Net-(Q2-G)") (class "Default")
      (node (ref "D4") (pin "A") (pinfunction "A_A") (pintype "passive"))
      (node (ref "D5") (pin "A") (pinfunction "A_A") (pintype "passive"))
      (node (ref "Q2") (pin "1") (pinfunction "G_1") (pintype "passive"))
    )
    (net (code "50") (name "Net-(Q3-D)") (class "Default")
      (node (ref "Q3") (pin "3") (pinfunction "D_3") (pintype "passive"))
      (node (ref "R15") (pin "2") (pinfunction "2_2") (pintype "passive"))
    )
    (net (code "51") (name "Net-(Q3-G)") (class "Default")
      (node (ref "D2") (pin "A") (pinfunction "A_A") (pintype "passive"))
      (node (ref "Q3") (pin "1") (pinfunction "G_1") (pintype "passive"))
    )
    (net (code "52") (name "Net-(Q4-D)") (class "Default")
      (node (ref "Q4") (pin "3") (pinfunction "D_3") (pintype "passive"))
      (node (ref "R36") (pin "2") (pinfunction "2_2") (pintype "passive"))
    )
    (net (code "53") (name "Net-(Q4-G)") (class "Default")
      (node (ref "D3") (pin "A") (pinfunction "A_A") (pintype "passive"))
      (node (ref "Q4") (pin "1") (pinfunction "G_1") (pintype "passive"))
    )
    (net (code "54") (name "Net-(Q5-D)") (class "Default")
      (node (ref "Q5") (pin "3") (pinfunction "D_3") (pintype "passive"))
      (node (ref "R28") (pin "2") (pinfunction "2_2") (pintype "passive"))
    )
    (net (code "55") (name "Net-(Q5-G)") (class "Default")
      (node (ref "D6") (pin "A") (pinfunction "A_A") (pintype "passive"))
      (node (ref "D7") (pin "A") (pinfunction "A_A") (pintype "passive"))
      (node (ref "Q5") (pin "1") (pinfunction "G_1") (pintype "passive"))
    )
    (net (code "56") (name "Net-(Q6-B)") (class "Default")
      (node (ref "C12") (pin "1") (pinfunction "1_1") (pintype "passive"))
      (node (ref "Q6") (pin "1") (pinfunction "B_1") (pintype "passive"))
      (node (ref "R24") (pin "2") (pinfunction "2_2") (pintype "passive"))
    )
    (net (code "57") (name "Net-(Q6-E)") (class "Default")
      (node (ref "C14") (pin "2") (pinfunction "2_2") (pintype "passive"))
      (node (ref "Q6") (pin "3") (pinfunction "E_3") (pintype "passive"))
      (node (ref "R25") (pin "2") (pinfunction "2_2") (pintype "passive"))
      (node (ref "R26") (pin "1") (pinfunction "1_1") (pintype "passive"))
    )
    (net (code "58") (name "Net-(Q7-B)") (class "Default")
      (node (ref "C15") (pin "+") (pinfunction "+_+") (pintype "passive"))
      (node (ref "Q7") (pin "1") (pinfunction "B_1") (pintype "passive"))
      (node (ref "R27") (pin "2") (pinfunction "2_2") (pintype "passive"))
    )
    (net (code "59") (name "Net-(Q8-B)") (class "Default")
      (node (ref "C22") (pin "1") (pinfunction "1_1") (pintype "passive"))
      (node (ref "Q8") (pin "1") (pinfunction "B_1") (pintype "passive"))
      (node (ref "R48") (pin "2") (pinfunction "2_2") (pintype "passive"))
    )
    (net (code "60") (name "Net-(Q8-E)") (class "Default")
      (node (ref "C21") (pin "2") (pinfunction "2_2") (pintype "passive"))
      (node (ref "C23") (pin "2") (pinfunction "2_2") (pintype "passive"))
      (node (ref "Q8") (pin "3") (pinfunction "E_3") (pintype "passive"))
      (node (ref "R37") (pin "2") (pinfunction "2_2") (pintype "passive"))
    )
    (net (code "61") (name "Net-(Q9-B)") (class "Default")
      (node (ref "Q9") (pin "1") (pinfunction "B_1") (pintype "passive"))
      (node (ref "R41") (pin "1") (pinfunction "1_1") (pintype "passive"))
    )
    (net (code "62") (name "Net-(Q9-C)") (class "Default")
      (node (ref "D11") (pin "C") (pinfunction "C_C") (pintype "passive"))
      (node (ref "Q9") (pin "2") (pinfunction "C_2") (pintype "passive"))
      (node (ref "R42") (pin "1") (pinfunction "1_1") (pintype "passive"))
    )
    (net (code "63") (name "Net-(Q10-B)") (class "Default")
      (node (ref "C26") (pin "1") (pinfunction "1_1") (pintype "passive"))
      (node (ref "Q10") (pin "1") (pinfunction "B_1") (pintype "passive"))
      (node (ref "R45") (pin "2") (pinfunction "2_2") (pintype "passive"))
    )
    (net (code "64") (name "Net-(Q10-E)") (class "Default")
      (node (ref "Q10") (pin "3") (pinfunction "E_3") (pintype "passive"))
      (node (ref "R44") (pin "2") (pinfunction "2_2") (pintype "passive"))
    )
    (net (code "65") (name "Net-(Q11-B)") (class "Default")
      (node (ref "C33") (pin "2") (pinfunction "2_2") (pintype "passive"))
      (node (ref "C34") (pin "1") (pinfunction "1_1") (pintype "passive"))
      (node (ref "Q11") (pin "1") (pinfunction "B_1") (pintype "passive"))
      (node (ref "R56") (pin "1") (pinfunction "1_1") (pintype "passive"))
      (node (ref "R57") (pin "2") (pinfunction "2_2") (pintype "passive"))
    )
    (net (code "66") (name "Net-(Q11-C)") (class "Default")
      (node (ref "C32") (pin "2") (pinfunction "2_2") (pintype "passive"))
      (node (ref "Q11") (pin "2") (pinfunction "C_2") (pintype "passive"))
      (node (ref "R55") (pin "1") (pinfunction "1_1") (pintype "passive"))
      (node (ref "R58") (pin "1") (pinfunction "1_1") (pintype "passive"))
      (node (ref "R61") (pin "1") (pinfunction "1_1") (pintype "passive"))
    )
    (net (code "67") (name "Net-(Q12-B)") (class "Default")
      (node (ref "C32") (pin "1") (pinfunction "1_1") (pintype "passive"))
      (node (ref "C35") (pin "1") (pinfunction "1_1") (pintype "passive"))
      (node (ref "Q12") (pin "1") (pinfunction "B_1") (pintype "passive"))
      (node (ref "R55") (pin "2") (pinfunction "2_2") (pintype "passive"))
      (node (ref "R60") (pin "2") (pinfunction "2_2") (pintype "passive"))
    )
    (net (code "68") (name "Net-(R10-Pad2)") (class "Default")
      (node (ref "R10") (pin "2") (pinfunction "2_2") (pintype "passive"))
      (node (ref "VR1") (pin "1") (pinfunction "1_1") (pintype "passive"))
    )
    (net (code "69") (name "Net-(R45-Pad1)") (class "Default")
      (node (ref "R45") (pin "1") (pinfunction "1_1") (pintype "passive"))
      (node (ref "VR2") (pin "2") (pinfunction "2_2") (pintype "passive"))
    )
    (net (code "70") (name "Net-(R52-Pad1)") (class "Default")
      (node (ref "R52") (pin "1") (pinfunction "1_1") (pintype "passive"))
      (node (ref "VR1") (pin "2") (pinfunction "2_2") (pintype "passive"))
    )
    (net (code "71") (name "Net-(R54-Pad2)") (class "Default")
      (node (ref "R54") (pin "2") (pinfunction "2_2") (pintype "passive"))
      (node (ref "VR3") (pin "1") (pinfunction "1_1") (pintype "passive"))
    )
    (net (code "72") (name "Net-(R64-Pad1)") (class "Default")
      (node (ref "R64") (pin "1") (pinfunction "1_1") (pintype "passive"))
      (node (ref "VR3") (pin "3") (pinfunction "3_3") (pintype "passive"))
    )
    (net (code "73") (name "Net-(SW1-O)") (class "Default")
      (node (ref "D2") (pin "C") (pinfunction "C_C") (pintype "passive"))
      (node (ref "D5") (pin "C") (pinfunction "C_C") (pintype "passive"))
      (node (ref "D7") (pin "C") (pinfunction "C_C") (pintype "passive"))
      (node (ref "R11") (pin "1") (pinfunction "1_1") (pintype "passive"))
      (node (ref "SW1") (pin "1") (pinfunction "O_1") (pintype "passive"))
    )
    (net (code "74") (name "Net-(SW1-P)") (class "Default")
      (node (ref "C9") (pin "1") (pinfunction "1_1") (pintype "passive"))
      (node (ref "R12") (pin "2") (pinfunction "2_2") (pintype "passive"))
      (node (ref "SW1") (pin "2") (pinfunction "P_2") (pintype "passive"))
    )
    (net (code "75") (name "Net-(SW2-S)") (class "Default")
      (node (ref "R63") (pin "1") (pinfunction "1_1") (pintype "passive"))
      (node (ref "SW2") (pin "2") (pinfunction "S_2") (pintype "passive"))
    )
    (net (code "76") (name "OUT") (class "Default")
      (node (ref "C7") (pin "-") (pinfunction "-_-") (pintype "passive"))
      (node (ref "C8") (pin "-") (pinfunction "-_-") (pintype "passive"))
      (node (ref "R5") (pin "2") (pinfunction "2_2") (pintype "passive"))
      (node (ref "R9") (pin "2") (pinfunction "2_2") (pintype "passive"))
    )
    (net (code "77") (name "VA") (class "Default")
      (node (ref "IC3") (pin "5") (pinfunction "5_5") (pintype "bidirectional"))
      (node (ref "IC4") (pin "1") (pinfunction "P$1_1") (pintype "bidirectional"))
      (node (ref "Q10") (pin "2") (pinfunction "C_2") (pintype "passive"))
      (node (ref "Q7") (pin "3") (pinfunction "E_3") (pintype "passive"))
      (node (ref "R40") (pin "2") (pinfunction "2_2") (pintype "passive"))
      (node (ref "R42") (pin "2") (pinfunction "2_2") (pintype "passive"))
      (node (ref "R46") (pin "2") (pinfunction "2_2") (pintype "passive"))
    )
    (net (code "78") (name "VB") (class "Default")
      (node (ref "C20") (pin "+") (pinfunction "+_+") (pintype "passive"))
      (node (ref "IC1") (pin "3") (pinfunction "+IN_3") (pintype "input"))
      (node (ref "IC2") (pin "3") (pinfunction "+IN_3") (pintype "input"))
      (node (ref "IC2") (pin "5") (pinfunction "+IN_5") (pintype "input"))
      (node (ref "R14") (pin "1") (pinfunction "1_1") (pintype "passive"))
      (node (ref "R16") (pin "1") (pinfunction "1_1") (pintype "passive"))
      (node (ref "R30") (pin "1") (pinfunction "1_1") (pintype "passive"))
      (node (ref "R35") (pin "1") (pinfunction "1_1") (pintype "passive"))
      (node (ref "R4") (pin "1") (pinfunction "1_1") (pintype "passive"))
      (node (ref "VR3") (pin "2") (pinfunction "2_2") (pintype "passive"))
    )
    (net (code "79") (name "VC") (class "Default")
      (node (ref "C27") (pin "+") (pinfunction "+_+") (pintype "passive"))
      (node (ref "IC5") (pin "5") (pinfunction "+IN_5") (pintype "input"))
      (node (ref "R10") (pin "1") (pinfunction "1_1") (pintype "passive"))
      (node (ref "R46") (pin "1") (pinfunction "1_1") (pintype "passive"))
      (node (ref "R50") (pin "2") (pinfunction "2_2") (pintype "passive"))
      (node (ref "R51") (pin "1") (pinfunction "1_1") (pintype "passive"))
      (node (ref "VR2") (pin "1") (pinfunction "1_1") (pintype "passive"))
    )
    (net (code "80") (name "unconnected-(IC4-P$6-Pad6)") (class "Default")
      (node (ref "IC4") (pin "6") (pinfunction "P$6_6") (pintype "bidirectional"))
    )
    (net (code "81") (name "unconnected-(SW1-S-Pad3)") (class "Default")
      (node (ref "SW1") (pin "3") (pinfunction "S_3") (pintype "passive"))
    )
  )
)
